# theremin-oscillator.net
KiCad netlist of a schematic drawn in EAGLE
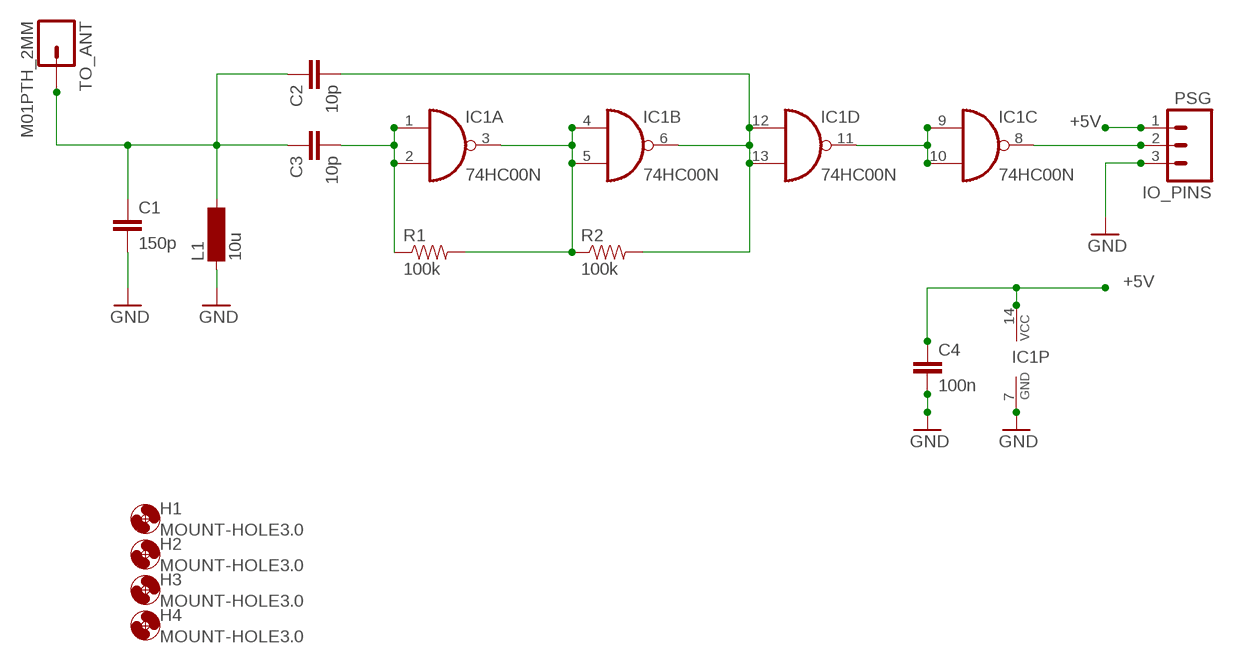
[diagram p0: schematic, sheet 1]

(export (version "E")
  (design (tool "Eeschema 10.0.6"))
  (components
    (comp (ref "C1")
      (value "150p")
      (footprint "eagle-import:CAP-PTH-SMALL")
      (libsource (lib "eagle-import") (part "CAPPTH"))
    )
    (comp (ref "C2")
      (value "10p")
      (footprint "eagle-import:CAP-PTH-SMALL")
      (libsource (lib "eagle-import") (part "CAPPTH"))
    )
    (comp (ref "C3")
      (value "10p")
      (footprint "eagle-import:CAP-PTH-SMALL")
      (libsource (lib "eagle-import") (part "CAPPTH"))
    )
    (comp (ref "C4")
      (value "100n")
      (footprint "eagle-import:CAP-PTH-SMALL")
      (libsource (lib "eagle-import") (part "CAPPTH"))
    )
    (comp (ref "H1")
      (value "MOUNT-HOLE3.0")
      (footprint "eagle-import:3,0")
      (libsource (lib "eagle-import") (part "MOUNT-HOLE3.0"))
    )
    (comp (ref "H2")
      (value "MOUNT-HOLE3.0")
      (footprint "eagle-import:3,0")
      (libsource (lib "eagle-import") (part "MOUNT-HOLE3.0"))
    )
    (comp (ref "H3")
      (value "MOUNT-HOLE3.0")
      (footprint "eagle-import:3,0")
      (libsource (lib "eagle-import") (part "MOUNT-HOLE3.0"))
    )
    (comp (ref "H4")
      (value "MOUNT-HOLE3.0")
      (footprint "eagle-import:3,0")
      (libsource (lib "eagle-import") (part "MOUNT-HOLE3.0"))
    )
    (comp (ref "IC1")
      (value "74HC00N")
      (footprint "eagle-import:DIL14")
      (libsource (lib "eagle-import") (part "7400NHC"))
    )
    (comp (ref "IO_PINS")
      (value "PSG")
      (footprint "eagle-import:1X03")
      (libsource (lib "eagle-import") (part "M03PTH"))
    )
    (comp (ref "L1")
      (value "10u")
      (footprint "eagle-import:BS11")
      (libsource (lib "eagle-import") (part "BS11"))
    )
    (comp (ref "R1")
      (value "100k")
      (footprint "eagle-import:AXIAL-0.4")
      (libsource (lib "eagle-import") (part "RESISTORPTH-1/4W"))
    )
    (comp (ref "R2")
      (value "100k")
      (footprint "eagle-import:AXIAL-0.4")
      (libsource (lib "eagle-import") (part "RESISTORPTH-1/4W"))
    )
    (comp (ref "TO_ANT")
      (value "M01PTH_2MM")
      (footprint "eagle-import:1X01_2MM")
      (libsource (lib "eagle-import") (part "M01PTH_2MM"))
    )
  )
  (nets
    (net (code "1") (name "/+5V") (class "Default")
      (node (ref "C4") (pin "1") (pinfunction "1_1") (pintype "passive"))
      (node (ref "IC1") (pin "14") (pinfunction "VCC_14") (pintype "power_in"))
      (node (ref "IO_PINS") (pin "1") (pinfunction "1_1") (pintype "passive"))
    )
    (net (code "2") (name "GND") (class "Default")
      (node (ref "C1") (pin "2") (pinfunction "2_2") (pintype "passive"))
      (node (ref "C4") (pin "2") (pinfunction "2_2") (pintype "passive"))
      (node (ref "IC1") (pin "7") (pinfunction "GND_7") (pintype "power_in"))
      (node (ref "IO_PINS") (pin "3") (pinfunction "3_3") (pintype "passive"))
      (node (ref "L1") (pin "1") (pinfunction "1_1") (pintype "passive"))
    )
    (net (code "3") (name "Net-(C1-Pad1)") (class "Default")
      (node (ref "C1") (pin "1") (pinfunction "1_1") (pintype "passive"))
      (node (ref "C2") (pin "1") (pinfunction "1_1") (pintype "passive"))
      (node (ref "C3") (pin "1") (pinfunction "1_1") (pintype "passive"))
      (node (ref "L1") (pin "2") (pinfunction "2_2") (pintype "passive"))
      (node (ref "TO_ANT") (pin "1") (pinfunction "1_1") (pintype "passive"))
    )
    (net (code "4") (name "Net-(IC1A-I0)") (class "Default")
      (node (ref "C3") (pin "2") (pinfunction "2_2") (pintype "passive"))
      (node (ref "IC1") (pin "1") (pinfunction "I0_1") (pintype "input"))
      (node (ref "IC1") (pin "2") (pinfunction "I1_2") (pintype "input"))
      (node (ref "R1") (pin "P$1") (pinfunction "1_P$1") (pintype "passive"))
    )
    (net (code "5") (name "Net-(IC1A-O)") (class "Default")
      (node (ref "IC1") (pin "3") (pinfunction "O_3") (pintype "output"))
      (node (ref "IC1") (pin "4") (pinfunction "I0_4") (pintype "input"))
      (node (ref "IC1") (pin "5") (pinfunction "I1_5") (pintype "input"))
      (node (ref "R1") (pin "P$2") (pinfunction "2_P$2") (pintype "passive"))
      (node (ref "R2") (pin "P$1") (pinfunction "1_P$1") (pintype "passive"))
    )
    (net (code "6") (name "Net-(IC1B-O)") (class "Default")
      (node (ref "C2") (pin "2") (pinfunction "2_2") (pintype "passive"))
      (node (ref "IC1") (pin "12") (pinfunction "I0_12") (pintype "input"))
      (node (ref "IC1") (pin "13") (pinfunction "I1_13") (pintype "input"))
      (node (ref "IC1") (pin "6") (pinfunction "O_6") (pintype "output"))
      (node (ref "R2") (pin "P$2") (pinfunction "2_P$2") (pintype "passive"))
    )
    (net (code "7") (name "Net-(IC1C-I0)") (class "Default")
      (node (ref "IC1") (pin "10") (pinfunction "I1_10") (pintype "input"))
      (node (ref "IC1") (pin "11") (pinfunction "O_11") (pintype "output"))
      (node (ref "IC1") (pin "9") (pinfunction "I0_9") (pintype "input"))
    )
    (net (code "8") (name "Net-(IC1C-O)") (class "Default")
      (node (ref "IC1") (pin "8") (pinfunction "O_8") (pintype "output"))
      (node (ref "IO_PINS") (pin "2") (pinfunction "2_2") (pintype "passive"))
    )
  )
)
